# Project13.net
KiCad netlist of a schematic drawn in EAGLE
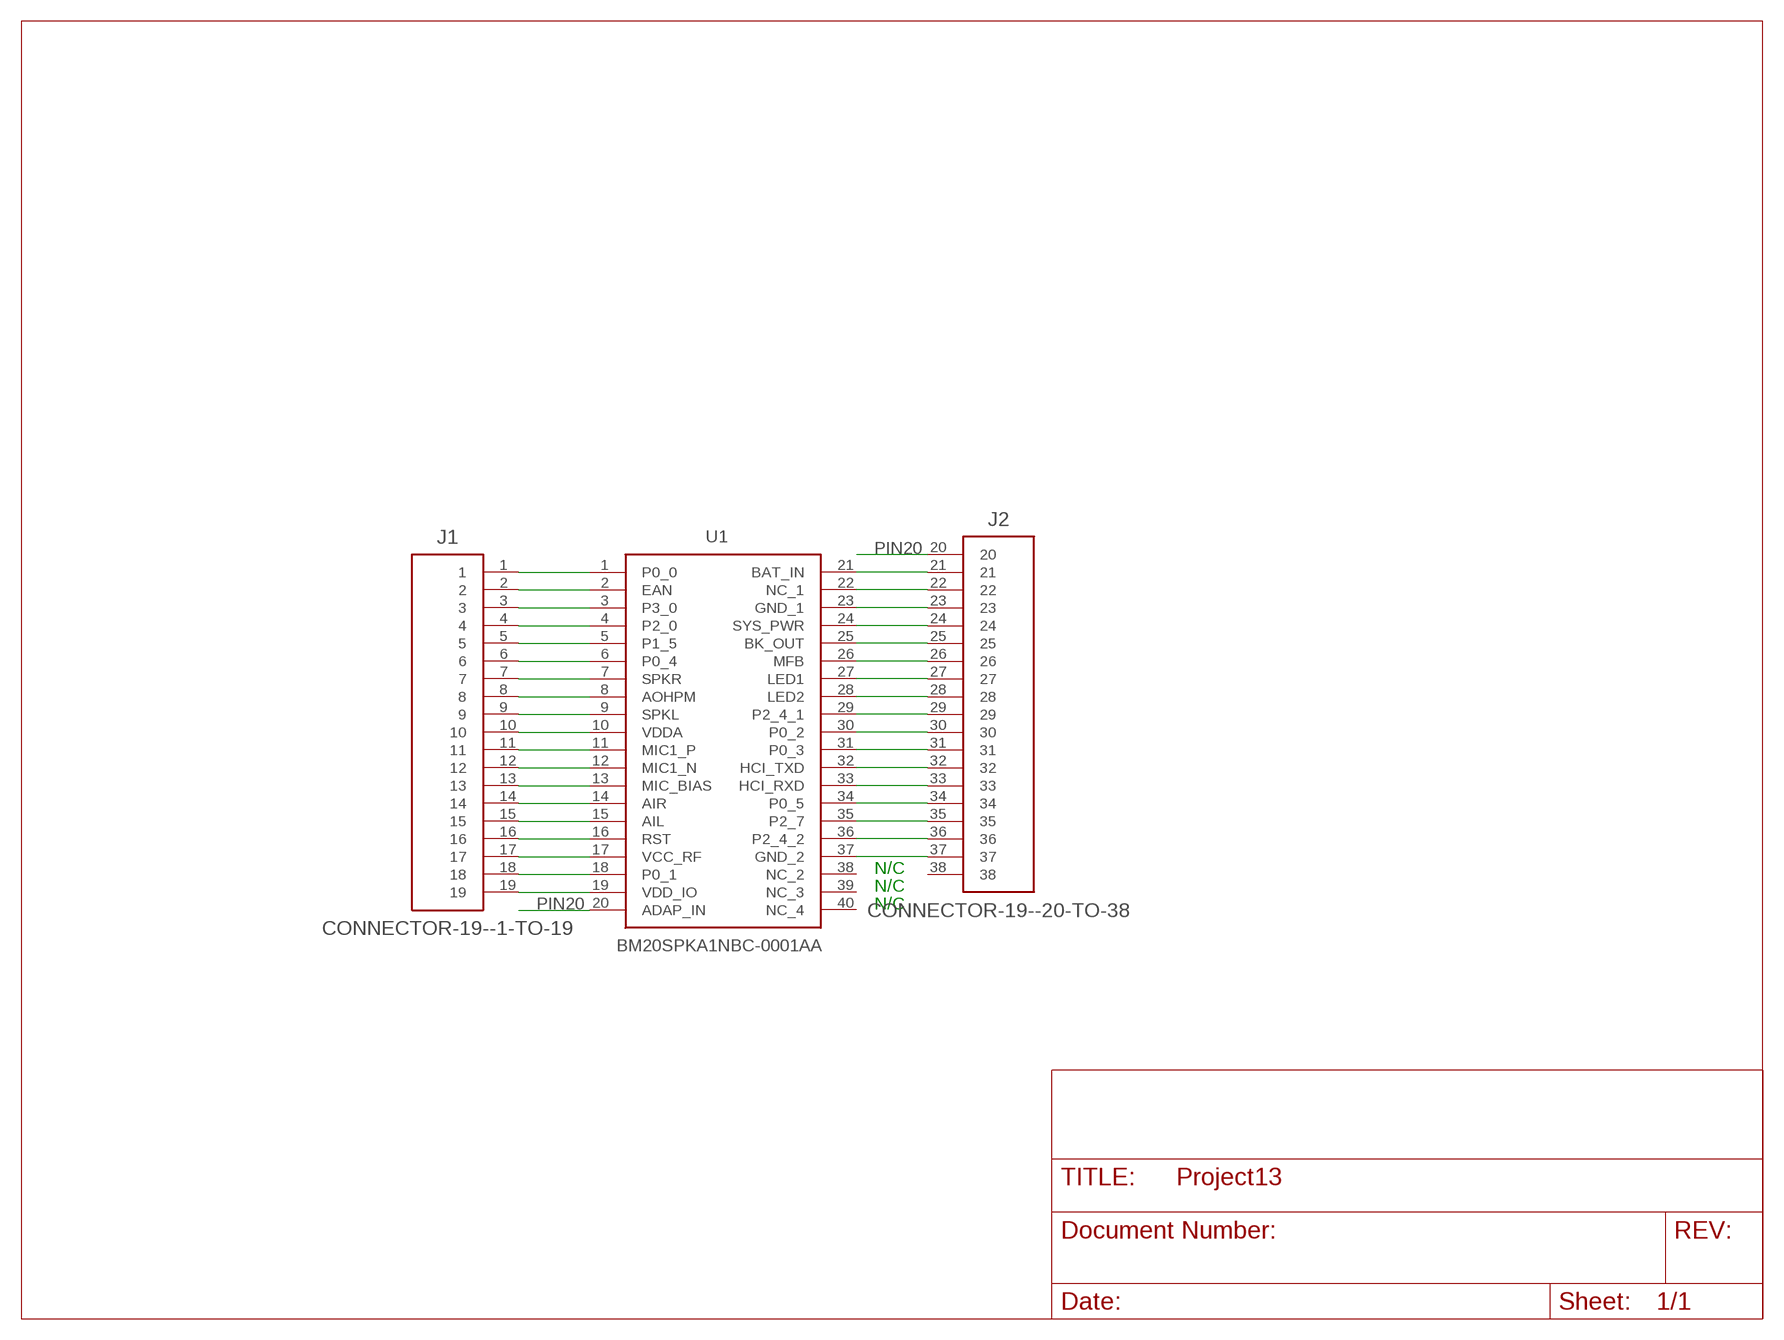
[diagram p0: schematic, sheet 1]

(export (version "E")
  (design (tool "Eeschema 10.0.6"))
  (components
    (comp (ref "J1")
      (value "CONNECTOR-19--1-TO-19")
      (footprint "eagle-import:ESQ-119-XX-XX-S")
      (libsource (lib "eagle-import") (part "CONNECTOR-19--1-TO-19"))
    )
    (comp (ref "J2")
      (value "CONNECTOR-19--20-TO-38")
      (footprint "eagle-import:ESQ-119-XX-XX-S--PIN-1-ROUND")
      (libsource (lib "eagle-import") (part "CONNECTOR-19--20-TO-38"))
    )
    (comp (ref "U1")
      (value "BM20SPKA1NBC-0001AA")
      (footprint "eagle-import:BM20SPKA1NBC0001AA")
      (fields (field (name "MOUSER_PART_NUMBER") "579-SPKA1NBC-0001AA"))
      (libsource (lib "eagle-import") (part "BM20SPKA1NBC-0001AA"))
    )
  )
  (nets
    (net (code "1") (name "/PIN20") (class "Default")
      (node (ref "J2") (pin "20") (pinfunction "20_20") (pintype "bidirectional"))
      (node (ref "U1") (pin "20") (pinfunction "ADAP_IN_20") (pintype "bidirectional"))
    )
    (net (code "2") (name "Net-(U1-AIL)") (class "Default")
      (node (ref "J1") (pin "15") (pinfunction "15_15") (pintype "bidirectional"))
      (node (ref "U1") (pin "15") (pinfunction "AIL_15") (pintype "bidirectional"))
    )
    (net (code "3") (name "Net-(U1-AIR)") (class "Default")
      (node (ref "J1") (pin "14") (pinfunction "14_14") (pintype "bidirectional"))
      (node (ref "U1") (pin "14") (pinfunction "AIR_14") (pintype "bidirectional"))
    )
    (net (code "4") (name "Net-(U1-AOHPM)") (class "Default")
      (node (ref "J1") (pin "8") (pinfunction "8_8") (pintype "bidirectional"))
      (node (ref "U1") (pin "8") (pinfunction "AOHPM_8") (pintype "bidirectional"))
    )
    (net (code "5") (name "Net-(U1-BAT_IN)") (class "Default")
      (node (ref "J2") (pin "21") (pinfunction "21_21") (pintype "bidirectional"))
      (node (ref "U1") (pin "21") (pinfunction "BAT_IN_21") (pintype "bidirectional"))
    )
    (net (code "6") (name "Net-(U1-BK_OUT)") (class "Default")
      (node (ref "J2") (pin "25") (pinfunction "25_25") (pintype "bidirectional"))
      (node (ref "U1") (pin "25") (pinfunction "BK_OUT_25") (pintype "bidirectional"))
    )
    (net (code "7") (name "Net-(U1-EAN)") (class "Default")
      (node (ref "J1") (pin "2") (pinfunction "2_2") (pintype "bidirectional"))
      (node (ref "U1") (pin "2") (pinfunction "EAN_2") (pintype "bidirectional"))
    )
    (net (code "8") (name "Net-(U1-GND_1)") (class "Default")
      (node (ref "J2") (pin "23") (pinfunction "23_23") (pintype "bidirectional"))
      (node (ref "U1") (pin "23") (pinfunction "GND_1_23") (pintype "bidirectional"))
    )
    (net (code "9") (name "Net-(U1-GND_2)") (class "Default")
      (node (ref "J2") (pin "37") (pinfunction "37_37") (pintype "bidirectional"))
      (node (ref "U1") (pin "37") (pinfunction "GND_2_37") (pintype "bidirectional"))
    )
    (net (code "10") (name "Net-(U1-HCI_RXD)") (class "Default")
      (node (ref "J2") (pin "33") (pinfunction "33_33") (pintype "bidirectional"))
      (node (ref "U1") (pin "33") (pinfunction "HCI_RXD_33") (pintype "bidirectional"))
    )
    (net (code "11") (name "Net-(U1-HCI_TXD)") (class "Default")
      (node (ref "J2") (pin "32") (pinfunction "32_32") (pintype "bidirectional"))
      (node (ref "U1") (pin "32") (pinfunction "HCI_TXD_32") (pintype "bidirectional"))
    )
    (net (code "12") (name "Net-(U1-LED1)") (class "Default")
      (node (ref "J2") (pin "27") (pinfunction "27_27") (pintype "bidirectional"))
      (node (ref "U1") (pin "27") (pinfunction "LED1_27") (pintype "bidirectional"))
    )
    (net (code "13") (name "Net-(U1-LED2)") (class "Default")
      (node (ref "J2") (pin "28") (pinfunction "28_28") (pintype "bidirectional"))
      (node (ref "U1") (pin "28") (pinfunction "LED2_28") (pintype "bidirectional"))
    )
    (net (code "14") (name "Net-(U1-MFB)") (class "Default")
      (node (ref "J2") (pin "26") (pinfunction "26_26") (pintype "bidirectional"))
      (node (ref "U1") (pin "26") (pinfunction "MFB_26") (pintype "bidirectional"))
    )
    (net (code "15") (name "Net-(U1-MIC1_N)") (class "Default")
      (node (ref "J1") (pin "12") (pinfunction "12_12") (pintype "bidirectional"))
      (node (ref "U1") (pin "12") (pinfunction "MIC1_N_12") (pintype "bidirectional"))
    )
    (net (code "16") (name "Net-(U1-MIC1_P)") (class "Default")
      (node (ref "J1") (pin "11") (pinfunction "11_11") (pintype "bidirectional"))
      (node (ref "U1") (pin "11") (pinfunction "MIC1_P_11") (pintype "bidirectional"))
    )
    (net (code "17") (name "Net-(U1-MIC_BIAS)") (class "Default")
      (node (ref "J1") (pin "13") (pinfunction "13_13") (pintype "bidirectional"))
      (node (ref "U1") (pin "13") (pinfunction "MIC_BIAS_13") (pintype "bidirectional"))
    )
    (net (code "18") (name "Net-(U1-NC_1)") (class "Default")
      (node (ref "J2") (pin "22") (pinfunction "22_22") (pintype "bidirectional"))
      (node (ref "U1") (pin "22") (pinfunction "NC_1_22") (pintype "bidirectional"))
    )
    (net (code "19") (name "Net-(U1-P0_0)") (class "Default")
      (node (ref "J1") (pin "1") (pinfunction "1_1") (pintype "bidirectional"))
      (node (ref "U1") (pin "1") (pinfunction "P0_0_1") (pintype "bidirectional"))
    )
    (net (code "20") (name "Net-(U1-P0_1)") (class "Default")
      (node (ref "J1") (pin "18") (pinfunction "18_18") (pintype "bidirectional"))
      (node (ref "U1") (pin "18") (pinfunction "P0_1_18") (pintype "bidirectional"))
    )
    (net (code "21") (name "Net-(U1-P0_2)") (class "Default")
      (node (ref "J2") (pin "30") (pinfunction "30_30") (pintype "bidirectional"))
      (node (ref "U1") (pin "30") (pinfunction "P0_2_30") (pintype "bidirectional"))
    )
    (net (code "22") (name "Net-(U1-P0_3)") (class "Default")
      (node (ref "J2") (pin "31") (pinfunction "31_31") (pintype "bidirectional"))
      (node (ref "U1") (pin "31") (pinfunction "P0_3_31") (pintype "bidirectional"))
    )
    (net (code "23") (name "Net-(U1-P0_4)") (class "Default")
      (node (ref "J1") (pin "6") (pinfunction "6_6") (pintype "bidirectional"))
      (node (ref "U1") (pin "6") (pinfunction "P0_4_6") (pintype "bidirectional"))
    )
    (net (code "24") (name "Net-(U1-P0_5)") (class "Default")
      (node (ref "J2") (pin "34") (pinfunction "34_34") (pintype "bidirectional"))
      (node (ref "U1") (pin "34") (pinfunction "P0_5_34") (pintype "bidirectional"))
    )
    (net (code "25") (name "Net-(U1-P1_5)") (class "Default")
      (node (ref "J1") (pin "5") (pinfunction "5_5") (pintype "bidirectional"))
      (node (ref "U1") (pin "5") (pinfunction "P1_5_5") (pintype "bidirectional"))
    )
    (net (code "26") (name "Net-(U1-P2_0)") (class "Default")
      (node (ref "J1") (pin "4") (pinfunction "4_4") (pintype "bidirectional"))
      (node (ref "U1") (pin "4") (pinfunction "P2_0_4") (pintype "bidirectional"))
    )
    (net (code "27") (name "Net-(U1-P2_4_1)") (class "Default")
      (node (ref "J2") (pin "29") (pinfunction "29_29") (pintype "bidirectional"))
      (node (ref "U1") (pin "29") (pinfunction "P2_4_1_29") (pintype "bidirectional"))
    )
    (net (code "28") (name "Net-(U1-P2_4_2)") (class "Default")
      (node (ref "J2") (pin "36") (pinfunction "36_36") (pintype "bidirectional"))
      (node (ref "U1") (pin "36") (pinfunction "P2_4_2_36") (pintype "bidirectional"))
    )
    (net (code "29") (name "Net-(U1-P2_7)") (class "Default")
      (node (ref "J2") (pin "35") (pinfunction "35_35") (pintype "bidirectional"))
      (node (ref "U1") (pin "35") (pinfunction "P2_7_35") (pintype "bidirectional"))
    )
    (net (code "30") (name "Net-(U1-P3_0)") (class "Default")
      (node (ref "J1") (pin "3") (pinfunction "3_3") (pintype "bidirectional"))
      (node (ref "U1") (pin "3") (pinfunction "P3_0_3") (pintype "bidirectional"))
    )
    (net (code "31") (name "Net-(U1-RST)") (class "Default")
      (node (ref "J1") (pin "16") (pinfunction "16_16") (pintype "bidirectional"))
      (node (ref "U1") (pin "16") (pinfunction "RST_16") (pintype "bidirectional"))
    )
    (net (code "32") (name "Net-(U1-SPKL)") (class "Default")
      (node (ref "J1") (pin "9") (pinfunction "9_9") (pintype "bidirectional"))
      (node (ref "U1") (pin "9") (pinfunction "SPKL_9") (pintype "bidirectional"))
    )
    (net (code "33") (name "Net-(U1-SPKR)") (class "Default")
      (node (ref "J1") (pin "7") (pinfunction "7_7") (pintype "bidirectional"))
      (node (ref "U1") (pin "7") (pinfunction "SPKR_7") (pintype "bidirectional"))
    )
    (net (code "34") (name "Net-(U1-SYS_PWR)") (class "Default")
      (node (ref "J2") (pin "24") (pinfunction "24_24") (pintype "bidirectional"))
      (node (ref "U1") (pin "24") (pinfunction "SYS_PWR_24") (pintype "bidirectional"))
    )
    (net (code "35") (name "Net-(U1-VCC_RF)") (class "Default")
      (node (ref "J1") (pin "17") (pinfunction "17_17") (pintype "bidirectional"))
      (node (ref "U1") (pin "17") (pinfunction "VCC_RF_17") (pintype "bidirectional"))
    )
    (net (code "36") (name "Net-(U1-VDDA)") (class "Default")
      (node (ref "J1") (pin "10") (pinfunction "10_10") (pintype "bidirectional"))
      (node (ref "U1") (pin "10") (pinfunction "VDDA_10") (pintype "bidirectional"))
    )
    (net (code "37") (name "Net-(U1-VDD_IO)") (class "Default")
      (node (ref "J1") (pin "19") (pinfunction "19_19") (pintype "bidirectional"))
      (node (ref "U1") (pin "19") (pinfunction "VDD_IO_19") (pintype "bidirectional"))
    )
    (net (code "38") (name "unconnected-(J2-Pad38)") (class "Default")
      (node (ref "J2") (pin "38") (pinfunction "38_38") (pintype "bidirectional"))
    )
    (net (code "39") (name "unconnected-(U1-NC_2-Pad38)") (class "Default")
      (node (ref "U1") (pin "38") (pinfunction "NC_2_38") (pintype "bidirectional"))
    )
    (net (code "40") (name "unconnected-(U1-NC_3-Pad39)") (class "Default")
      (node (ref "U1") (pin "39") (pinfunction "NC_3_39") (pintype "bidirectional"))
    )
    (net (code "41") (name "unconnected-(U1-NC_4-Pad40)") (class "Default")
      (node (ref "U1") (pin "40") (pinfunction "NC_4_40") (pintype "bidirectional"))
    )
  )
)
